# ZENDER.net
KiCad netlist of a schematic drawn in Altium Designer
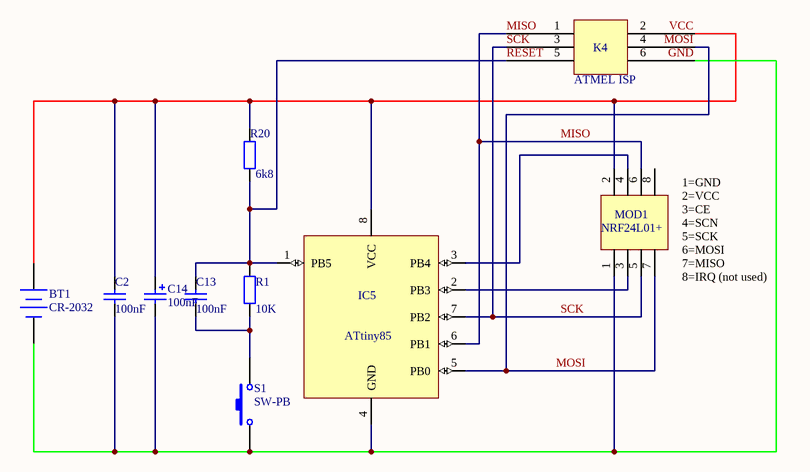
[diagram p0: ZENDER.SchDoc]

(export (version "E")
  (design (tool "Eeschema 10.0.6"))
  (components
    (comp (ref "BT1")
      (value "CR-2032")
      (footprint "PANA-CR-2032HFN")
      (description "Coin Cell Battery, 225 mAh, 0.2 mA, 3 V, -30 to 60 degC, Bulk")
      (fields (field (name "MANUFACTURER") "Panasonic"))
      (libsource (lib "Altium Content Vault") (part "BATTERY_SINGLE-2"))
    )
    (comp (ref "C2")
      (value "100nF")
      (footprint "C1206")
      (description "Capacitor (Semiconductor SIM Model)")
      (fields (field (name "Comment") "Cap Semi") (field (name "PUBLISHER") "Altium Limited"))
      (libsource (lib "Miscellaneous Devices") (part "Cap Semi"))
    )
    (comp (ref "C13")
      (value "100nF")
      (footprint "C1206")
      (description "Capacitor (Semiconductor SIM Model)")
      (fields (field (name "Comment") "Cap Semi") (field (name "PUBLISHER") "Altium Limited"))
      (libsource (lib "Miscellaneous Devices") (part "Cap Semi"))
    )
    (comp (ref "C14")
      (value "100nF")
      (footprint "POLAR0.8")
      (description "Polarized Capacitor (Axial)")
      (fields (field (name "Comment") "Cap Pol2") (field (name "PUBLISHER") "Altium Limited"))
      (libsource (lib "PCB_Project_ZENDER") (part "Cap Pol2"))
    )
    (comp (ref "IC5")
      (value "ATtiny85")
      (footprint "*SOIC127P798X216-8N")
      (fields
        (field (name "MANUFACTURER") "Microchip / Atmel")
        (field (name "MANUFACTURER PART NUMBER") "ATTINY85-20PU")
      )
      (libsource (lib "PCB_Project_ZENDER") (part "CMP-0093-00032-2"))
    )
    (comp (ref "K4")
      (value "ATMEL ISP")
      (footprint "HDR2X3")
      (description "Header, 3-Pin, Dual row")
      (fields (field (name "PUBLISHER") "Altium Limited"))
      (libsource (lib "Miscellaneous Connectors") (part "Header 3X2"))
    )
    (comp (ref "MOD1")
      (value "NRF24L01+")
      (footprint "HDR2X4")
      (description "Header, 4-Pin, Dual row")
      (fields (field (name "PUBLISHER") "Altium Limited"))
      (libsource (lib "Miscellaneous Connectors") (part "Header 4X2"))
    )
    (comp (ref "R1")
      (value "10K")
      (footprint "*RESC3115X70N")
      (description "Resistor")
      (fields (field (name "Comment") "Res2") (field (name "PUBLISHER") "Altium Limited"))
      (libsource (lib "Miscellaneous Devices") (part "Res2"))
    )
    (comp (ref "R20")
      (value "6k8")
      (footprint "*RESC3216X55N")
      (description "Resistor")
      (fields (field (name "Comment") "Res2") (field (name "PUBLISHER") "Altium Limited"))
      (libsource (lib "Miscellaneous Devices") (part "Res2"))
    )
    (comp (ref "S1")
      (value "SW-PB")
      (footprint "SPST-2")
      (description "Switch")
      (fields (field (name "PUBLISHER") "Altium Limited"))
      (libsource (lib "Miscellaneous Devices") (part "SW-PB"))
    )
  )
  (nets
    (net (code "1") (name "Net-(BT1-+)") (class "Default")
      (node (ref "BT1") (pin "1") (pinfunction "+_1") (pintype "passive"))
      (node (ref "C14") (pin "1") (pinfunction "1_1") (pintype "passive"))
      (node (ref "C2") (pin "2") (pinfunction "2_2") (pintype "passive"))
      (node (ref "IC5") (pin "8") (pinfunction "VCC_8") (pintype "power_in"))
      (node (ref "K4") (pin "2") (pintype "passive"))
      (node (ref "MOD1") (pin "2") (pintype "passive"))
      (node (ref "R20") (pin "1") (pinfunction "1_1") (pintype "passive"))
    )
    (net (code "2") (name "Net-(BT1--)") (class "Default")
      (node (ref "BT1") (pin "2") (pinfunction "-_2") (pintype "passive"))
      (node (ref "C14") (pin "2") (pinfunction "2_2") (pintype "passive"))
      (node (ref "C2") (pin "1") (pinfunction "1_1") (pintype "passive"))
      (node (ref "IC5") (pin "4") (pinfunction "GND_4") (pintype "power_in"))
      (node (ref "K4") (pin "6") (pintype "passive"))
      (node (ref "MOD1") (pin "1") (pintype "passive"))
      (node (ref "S1") (pin "1") (pinfunction "1_1") (pintype "passive"))
    )
    (net (code "3") (name "Net-(C13-Pad1)") (class "Default")
      (node (ref "C13") (pin "1") (pinfunction "1_1") (pintype "passive"))
      (node (ref "R1") (pin "2") (pinfunction "2_2") (pintype "passive"))
      (node (ref "S1") (pin "2") (pinfunction "2_2") (pintype "passive"))
    )
    (net (code "4") (name "Net-(IC5-PB0)") (class "Default")
      (node (ref "IC5") (pin "5") (pinfunction "PB0_5") (pintype "bidirectional"))
      (node (ref "K4") (pin "4") (pintype "passive"))
      (node (ref "MOD1") (pin "7") (pintype "passive"))
    )
    (net (code "5") (name "Net-(IC5-PB1)") (class "Default")
      (node (ref "IC5") (pin "6") (pinfunction "PB1_6") (pintype "bidirectional"))
      (node (ref "K4") (pin "1") (pintype "passive"))
      (node (ref "MOD1") (pin "6") (pintype "passive"))
    )
    (net (code "6") (name "Net-(IC5-PB2)") (class "Default")
      (node (ref "IC5") (pin "7") (pinfunction "PB2_7") (pintype "bidirectional"))
      (node (ref "K4") (pin "3") (pintype "passive"))
      (node (ref "MOD1") (pin "5") (pintype "passive"))
    )
    (net (code "7") (name "Net-(IC5-PB3)") (class "Default")
      (node (ref "IC5") (pin "2") (pinfunction "PB3_2") (pintype "bidirectional"))
      (node (ref "MOD1") (pin "3") (pintype "passive"))
    )
    (net (code "8") (name "Net-(IC5-PB4)") (class "Default")
      (node (ref "IC5") (pin "3") (pinfunction "PB4_3") (pintype "bidirectional"))
      (node (ref "MOD1") (pin "4") (pintype "passive"))
    )
    (net (code "9") (name "Net-(IC5-PB5)") (class "Default")
      (node (ref "C13") (pin "2") (pinfunction "2_2") (pintype "passive"))
      (node (ref "IC5") (pin "1") (pinfunction "PB5_1") (pintype "bidirectional"))
      (node (ref "K4") (pin "5") (pintype "passive"))
      (node (ref "R1") (pin "1") (pinfunction "1_1") (pintype "passive"))
      (node (ref "R20") (pin "2") (pinfunction "2_2") (pintype "passive"))
    )
    (net (code "10") (name "unconnected-(MOD1-Pad8)") (class "Default")
      (node (ref "MOD1") (pin "8") (pintype "passive"))
    )
  )
)
